# FPGA_Banks_DDR3.net
KiCad netlist of a schematic drawn in Altium Designer
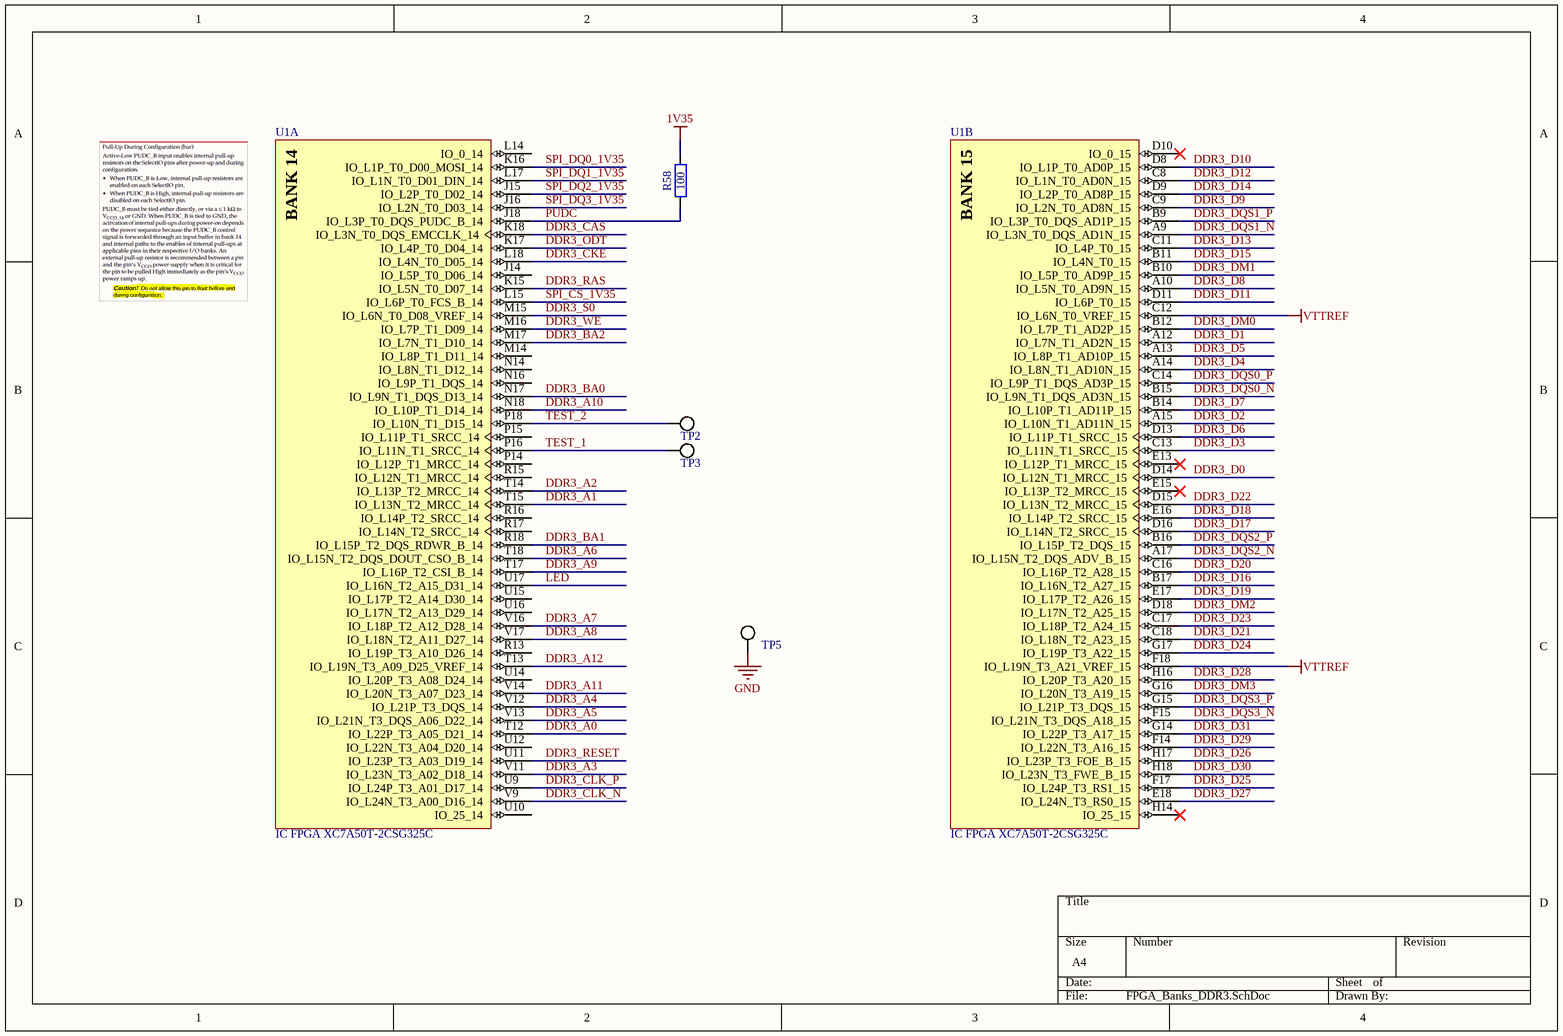
[diagram p0: FPGA_Banks_DDR3.SchDoc]

(export (version "E")
  (design (tool "Eeschema 10.0.6"))
  (components
    (comp (ref "R58")
      (value "100")
      (footprint "GEN_R_0201")
      (fields
        (field (name "TOLERANCE") "1%")
        (field (name "HOUSE PART NUMBER") "R-100-0201-1%-001")
        (field (name "MANUFACTURER") "Yageo")
      )
      (libsource (lib "DSO") (part "RES 100 OHM 1% 1/20W 0201"))
    )
    (comp (ref "TP2") (value "PCB") (footprint "GEN_TP_PCB") (libsource (lib "DSO") (part "TP PCB 1mm")))
    (comp (ref "TP3") (value "PCB") (footprint "GEN_TP_PCB") (libsource (lib "DSO") (part "TP PCB 1mm")))
    (comp (ref "TP5") (value "PCB") (footprint "GEN_TP_PCB") (libsource (lib "DSO") (part "TP PCB 1mm")))
    (comp (ref "U1")
      (value "IC FPGA XC7A50T-2CSG325C")
      (footprint "XILINX_XC7A50T-2CSG325C")
      (description "Artix-7 FPGA, 150 User I/Os, 4 GTP, 324-Ball BGA, Speed Grade 2, Commercial Grade, Pb-Free")
      (fields (field (name "MANUFACTURER") "Xilinx") (field (name "HOUSE PART NUMBER") "XC7A50T-2CSG325C"))
      (libsource (lib "DSO") (part "IC FPGA XC7A50T-2CSG325C"))
    )
  )
  (nets
    (net (code "1") (name "/DDR3_A0") (class "Default")
      (node (ref "U1") (pin "T12") (pinfunction "IO_L22P_T3_A05_D21_14_T12") (pintype "bidirectional"))
    )
    (net (code "2") (name "/DDR3_A1") (class "Default")
      (node (ref "U1") (pin "T15") (pinfunction "IO_L13N_T2_MRCC_14_T15") (pintype "bidirectional"))
    )
    (net (code "3") (name "/DDR3_A2") (class "Default")
      (node (ref "U1") (pin "T14") (pinfunction "IO_L13P_T2_MRCC_14_T14") (pintype "bidirectional"))
    )
    (net (code "4") (name "/DDR3_A3") (class "Default")
      (node (ref "U1") (pin "V11") (pinfunction "IO_L23N_T3_A02_D18_14_V11") (pintype "bidirectional"))
    )
    (net (code "5") (name "/DDR3_A4") (class "Default")
      (node (ref "U1") (pin "V12") (pinfunction "IO_L21P_T3_DQS_14_V12") (pintype "bidirectional"))
    )
    (net (code "6") (name "/DDR3_A5") (class "Default")
      (node (ref "U1") (pin "V13") (pinfunction "IO_L21N_T3_DQS_A06_D22_14_V13") (pintype "bidirectional"))
    )
    (net (code "7") (name "/DDR3_A6") (class "Default")
      (node (ref "U1") (pin "T18") (pinfunction "IO_L15N_T2_DQS_DOUT_CSO_B_14_T18") (pintype "bidirectional"))
    )
    (net (code "8") (name "/DDR3_A7") (class "Default")
      (node (ref "U1") (pin "V16") (pinfunction "IO_L18P_T2_A12_D28_14_V16") (pintype "bidirectional"))
    )
    (net (code "9") (name "/DDR3_A8") (class "Default")
      (node (ref "U1") (pin "V17") (pinfunction "IO_L18N_T2_A11_D27_14_V17") (pintype "bidirectional"))
    )
    (net (code "10") (name "/DDR3_A9") (class "Default")
      (node (ref "U1") (pin "T17") (pinfunction "IO_L16P_T2_CSI_B_14_T17") (pintype "bidirectional"))
    )
    (net (code "11") (name "/DDR3_A10") (class "Default")
      (node (ref "U1") (pin "N18") (pinfunction "IO_L10P_T1_D14_14_N18") (pintype "bidirectional"))
    )
    (net (code "12") (name "/DDR3_A11") (class "Default")
      (node (ref "U1") (pin "V14") (pinfunction "IO_L20N_T3_A07_D23_14_V14") (pintype "bidirectional"))
    )
    (net (code "13") (name "/DDR3_A12") (class "Default")
      (node (ref "U1") (pin "T13") (pinfunction "IO_L19N_T3_A09_D25_VREF_14_T13") (pintype "bidirectional"))
    )
    (net (code "14") (name "/DDR3_BA0") (class "Default")
      (node (ref "U1") (pin "N17") (pinfunction "IO_L9N_T1_DQS_D13_14_N17") (pintype "bidirectional"))
    )
    (net (code "15") (name "/DDR3_BA1") (class "Default")
      (node (ref "U1") (pin "R18") (pinfunction "IO_L15P_T2_DQS_RDWR_B_14_R18") (pintype "bidirectional"))
    )
    (net (code "16") (name "/DDR3_BA2") (class "Default")
      (node (ref "U1") (pin "M17") (pinfunction "IO_L7N_T1_D10_14_M17") (pintype "bidirectional"))
    )
    (net (code "17") (name "/DDR3_CAS") (class "Default")
      (node (ref "U1") (pin "K18") (pinfunction "IO_L3N_T0_DQS_EMCCLK_14_K18") (pintype "bidirectional"))
    )
    (net (code "18") (name "/DDR3_CKE") (class "Default")
      (node (ref "U1") (pin "L18") (pinfunction "IO_L4N_T0_D05_14_L18") (pintype "bidirectional"))
    )
    (net (code "19") (name "/DDR3_CLK_N") (class "Default")
      (node (ref "U1") (pin "V9") (pinfunction "IO_L24N_T3_A00_D16_14_V9") (pintype "bidirectional"))
    )
    (net (code "20") (name "/DDR3_CLK_P") (class "Default")
      (node (ref "U1") (pin "U9") (pinfunction "IO_L24P_T3_A01_D17_14_U9") (pintype "bidirectional"))
    )
    (net (code "21") (name "/DDR3_D0") (class "Default")
      (node (ref "U1") (pin "D14") (pinfunction "IO_L12N_T1_MRCC_15_D14") (pintype "bidirectional"))
    )
    (net (code "22") (name "/DDR3_D1") (class "Default")
      (node (ref "U1") (pin "A12") (pinfunction "IO_L7N_T1_AD2N_15_A12") (pintype "bidirectional"))
    )
    (net (code "23") (name "/DDR3_D2") (class "Default")
      (node (ref "U1") (pin "A15") (pinfunction "IO_L10N_T1_AD11N_15_A15") (pintype "bidirectional"))
    )
    (net (code "24") (name "/DDR3_D3") (class "Default")
      (node (ref "U1") (pin "C13") (pinfunction "IO_L11N_T1_SRCC_15_C13") (pintype "bidirectional"))
    )
    (net (code "25") (name "/DDR3_D4") (class "Default")
      (node (ref "U1") (pin "A14") (pinfunction "IO_L8N_T1_AD10N_15_A14") (pintype "bidirectional"))
    )
    (net (code "26") (name "/DDR3_D5") (class "Default")
      (node (ref "U1") (pin "A13") (pinfunction "IO_L8P_T1_AD10P_15_A13") (pintype "bidirectional"))
    )
    (net (code "27") (name "/DDR3_D6") (class "Default")
      (node (ref "U1") (pin "D13") (pinfunction "IO_L11P_T1_SRCC_15_D13") (pintype "bidirectional"))
    )
    (net (code "28") (name "/DDR3_D7") (class "Default")
      (node (ref "U1") (pin "B14") (pinfunction "IO_L10P_T1_AD11P_15_B14") (pintype "bidirectional"))
    )
    (net (code "29") (name "/DDR3_D8") (class "Default")
      (node (ref "U1") (pin "A10") (pinfunction "IO_L5N_T0_AD9N_15_A10") (pintype "bidirectional"))
    )
    (net (code "30") (name "/DDR3_D9") (class "Default")
      (node (ref "U1") (pin "C9") (pinfunction "IO_L2N_T0_AD8N_15_C9") (pintype "bidirectional"))
    )
    (net (code "31") (name "/DDR3_D10") (class "Default")
      (node (ref "U1") (pin "D8") (pinfunction "IO_L1P_T0_AD0P_15_D8") (pintype "bidirectional"))
    )
    (net (code "32") (name "/DDR3_D11") (class "Default")
      (node (ref "U1") (pin "D11") (pinfunction "IO_L6P_T0_15_D11") (pintype "bidirectional"))
    )
    (net (code "33") (name "/DDR3_D12") (class "Default")
      (node (ref "U1") (pin "C8") (pinfunction "IO_L1N_T0_AD0N_15_C8") (pintype "bidirectional"))
    )
    (net (code "34") (name "/DDR3_D13") (class "Default")
      (node (ref "U1") (pin "C11") (pinfunction "IO_L4P_T0_15_C11") (pintype "bidirectional"))
    )
    (net (code "35") (name "/DDR3_D14") (class "Default")
      (node (ref "U1") (pin "D9") (pinfunction "IO_L2P_T0_AD8P_15_D9") (pintype "bidirectional"))
    )
    (net (code "36") (name "/DDR3_D15") (class "Default")
      (node (ref "U1") (pin "B11") (pinfunction "IO_L4N_T0_15_B11") (pintype "bidirectional"))
    )
    (net (code "37") (name "/DDR3_D16") (class "Default")
      (node (ref "U1") (pin "B17") (pinfunction "IO_L16N_T2_A27_15_B17") (pintype "bidirectional"))
    )
    (net (code "38") (name "/DDR3_D17") (class "Default")
      (node (ref "U1") (pin "D16") (pinfunction "IO_L14N_T2_SRCC_15_D16") (pintype "bidirectional"))
    )
    (net (code "39") (name "/DDR3_D18") (class "Default")
      (node (ref "U1") (pin "E16") (pinfunction "IO_L14P_T2_SRCC_15_E16") (pintype "bidirectional"))
    )
    (net (code "40") (name "/DDR3_D19") (class "Default")
      (node (ref "U1") (pin "E17") (pinfunction "IO_L17P_T2_A26_15_E17") (pintype "bidirectional"))
    )
    (net (code "41") (name "/DDR3_D20") (class "Default")
      (node (ref "U1") (pin "C16") (pinfunction "IO_L16P_T2_A28_15_C16") (pintype "bidirectional"))
    )
    (net (code "42") (name "/DDR3_D21") (class "Default")
      (node (ref "U1") (pin "C18") (pinfunction "IO_L18N_T2_A23_15_C18") (pintype "bidirectional"))
    )
    (net (code "43") (name "/DDR3_D22") (class "Default")
      (node (ref "U1") (pin "D15") (pinfunction "IO_L13N_T2_MRCC_15_D15") (pintype "bidirectional"))
    )
    (net (code "44") (name "/DDR3_D23") (class "Default")
      (node (ref "U1") (pin "C17") (pinfunction "IO_L18P_T2_A24_15_C17") (pintype "bidirectional"))
    )
    (net (code "45") (name "/DDR3_D24") (class "Default")
      (node (ref "U1") (pin "G17") (pinfunction "IO_L19P_T3_A22_15_G17") (pintype "bidirectional"))
    )
    (net (code "46") (name "/DDR3_D25") (class "Default")
      (node (ref "U1") (pin "F17") (pinfunction "IO_L24P_T3_RS1_15_F17") (pintype "bidirectional"))
    )
    (net (code "47") (name "/DDR3_D26") (class "Default")
      (node (ref "U1") (pin "H17") (pinfunction "IO_L23P_T3_FOE_B_15_H17") (pintype "bidirectional"))
    )
    (net (code "48") (name "/DDR3_D27") (class "Default")
      (node (ref "U1") (pin "E18") (pinfunction "IO_L24N_T3_RS0_15_E18") (pintype "bidirectional"))
    )
    (net (code "49") (name "/DDR3_D28") (class "Default")
      (node (ref "U1") (pin "H16") (pinfunction "IO_L20P_T3_A20_15_H16") (pintype "bidirectional"))
    )
    (net (code "50") (name "/DDR3_D29") (class "Default")
      (node (ref "U1") (pin "F14") (pinfunction "IO_L22N_T3_A16_15_F14") (pintype "bidirectional"))
    )
    (net (code "51") (name "/DDR3_D30") (class "Default")
      (node (ref "U1") (pin "H18") (pinfunction "IO_L23N_T3_FWE_B_15_H18") (pintype "bidirectional"))
    )
    (net (code "52") (name "/DDR3_D31") (class "Default")
      (node (ref "U1") (pin "G14") (pinfunction "IO_L22P_T3_A17_15_G14") (pintype "bidirectional"))
    )
    (net (code "53") (name "/DDR3_DM0") (class "Default")
      (node (ref "U1") (pin "B12") (pinfunction "IO_L7P_T1_AD2P_15_B12") (pintype "bidirectional"))
    )
    (net (code "54") (name "/DDR3_DM1") (class "Default")
      (node (ref "U1") (pin "B10") (pinfunction "IO_L5P_T0_AD9P_15_B10") (pintype "bidirectional"))
    )
    (net (code "55") (name "/DDR3_DM2") (class "Default")
      (node (ref "U1") (pin "D18") (pinfunction "IO_L17N_T2_A25_15_D18") (pintype "bidirectional"))
    )
    (net (code "56") (name "/DDR3_DM3") (class "Default")
      (node (ref "U1") (pin "G16") (pinfunction "IO_L20N_T3_A19_15_G16") (pintype "bidirectional"))
    )
    (net (code "57") (name "/DDR3_DQS0_N") (class "Default")
      (node (ref "U1") (pin "B15") (pinfunction "IO_L9N_T1_DQS_AD3N_15_B15") (pintype "bidirectional"))
    )
    (net (code "58") (name "/DDR3_DQS0_P") (class "Default")
      (node (ref "U1") (pin "C14") (pinfunction "IO_L9P_T1_DQS_AD3P_15_C14") (pintype "bidirectional"))
    )
    (net (code "59") (name "/DDR3_DQS1_N") (class "Default")
      (node (ref "U1") (pin "A9") (pinfunction "IO_L3N_T0_DQS_AD1N_15_A9") (pintype "bidirectional"))
    )
    (net (code "60") (name "/DDR3_DQS1_P") (class "Default")
      (node (ref "U1") (pin "B9") (pinfunction "IO_L3P_T0_DQS_AD1P_15_B9") (pintype "bidirectional"))
    )
    (net (code "61") (name "/DDR3_DQS2_N") (class "Default")
      (node (ref "U1") (pin "A17") (pinfunction "IO_L15N_T2_DQS_ADV_B_15_A17") (pintype "bidirectional"))
    )
    (net (code "62") (name "/DDR3_DQS2_P") (class "Default")
      (node (ref "U1") (pin "B16") (pinfunction "IO_L15P_T2_DQS_15_B16") (pintype "bidirectional"))
    )
    (net (code "63") (name "/DDR3_DQS3_N") (class "Default")
      (node (ref "U1") (pin "F15") (pinfunction "IO_L21N_T3_DQS_A18_15_F15") (pintype "bidirectional"))
    )
    (net (code "64") (name "/DDR3_DQS3_P") (class "Default")
      (node (ref "U1") (pin "G15") (pinfunction "IO_L21P_T3_DQS_15_G15") (pintype "bidirectional"))
    )
    (net (code "65") (name "/DDR3_ODT") (class "Default")
      (node (ref "U1") (pin "K17") (pinfunction "IO_L4P_T0_D04_14_K17") (pintype "bidirectional"))
    )
    (net (code "66") (name "/DDR3_RAS") (class "Default")
      (node (ref "U1") (pin "K15") (pinfunction "IO_L5N_T0_D07_14_K15") (pintype "bidirectional"))
    )
    (net (code "67") (name "/DDR3_RESET") (class "Default")
      (node (ref "U1") (pin "U11") (pinfunction "IO_L23P_T3_A03_D19_14_U11") (pintype "bidirectional"))
    )
    (net (code "68") (name "/DDR3_S0") (class "Default")
      (node (ref "U1") (pin "M15") (pinfunction "IO_L6N_T0_D08_VREF_14_M15") (pintype "bidirectional"))
    )
    (net (code "69") (name "/DDR3_WE") (class "Default")
      (node (ref "U1") (pin "M16") (pinfunction "IO_L7P_T1_D09_14_M16") (pintype "bidirectional"))
    )
    (net (code "70") (name "/LED") (class "Default")
      (node (ref "U1") (pin "U17") (pinfunction "IO_L16N_T2_A15_D31_14_U17") (pintype "bidirectional"))
    )
    (net (code "71") (name "/PUDC") (class "Default")
      (node (ref "R58") (pin "1") (pinfunction "1_1") (pintype "passive"))
      (node (ref "U1") (pin "J18") (pinfunction "IO_L3P_T0_DQS_PUDC_B_14_J18") (pintype "bidirectional"))
    )
    (net (code "72") (name "/SPI_CS_1V35") (class "Default")
      (node (ref "U1") (pin "L15") (pinfunction "IO_L6P_T0_FCS_B_14_L15") (pintype "bidirectional"))
    )
    (net (code "73") (name "/SPI_DQ0_1V35") (class "Default")
      (node (ref "U1") (pin "K16") (pinfunction "IO_L1P_T0_D00_MOSI_14_K16") (pintype "bidirectional"))
    )
    (net (code "74") (name "/SPI_DQ1_1V35") (class "Default")
      (node (ref "U1") (pin "L17") (pinfunction "IO_L1N_T0_D01_DIN_14_L17") (pintype "bidirectional"))
    )
    (net (code "75") (name "/SPI_DQ2_1V35") (class "Default")
      (node (ref "U1") (pin "J15") (pinfunction "IO_L2P_T0_D02_14_J15") (pintype "bidirectional"))
    )
    (net (code "76") (name "/SPI_DQ3_1V35") (class "Default")
      (node (ref "U1") (pin "J16") (pinfunction "IO_L2N_T0_D03_14_J16") (pintype "bidirectional"))
    )
    (net (code "77") (name "/TEST_1") (class "Default")
      (node (ref "TP3") (pin "1") (pinfunction "1_1") (pintype "passive"))
      (node (ref "U1") (pin "P16") (pinfunction "IO_L11N_T1_SRCC_14_P16") (pintype "bidirectional"))
    )
    (net (code "78") (name "/TEST_2") (class "Default")
      (node (ref "TP2") (pin "1") (pinfunction "1_1") (pintype "passive"))
      (node (ref "U1") (pin "P18") (pinfunction "IO_L10N_T1_D15_14_P18") (pintype "bidirectional"))
    )
    (net (code "79") (name "1V35") (class "Default")
      (node (ref "R58") (pin "2") (pinfunction "2_2") (pintype "passive"))
    )
    (net (code "80") (name "GND") (class "Default")
      (node (ref "TP5") (pin "1") (pinfunction "1_1") (pintype "passive"))
    )
    (net (code "81") (name "VTTREF") (class "Default")
      (node (ref "U1") (pin "C12") (pinfunction "IO_L6N_T0_VREF_15_C12") (pintype "bidirectional"))
      (node (ref "U1") (pin "F18") (pinfunction "IO_L19N_T3_A21_VREF_15_F18") (pintype "bidirectional"))
    )
    (net (code "82") (name "unconnected-(U1A-IO_0_14-PadL14)") (class "Default")
      (node (ref "U1") (pin "L14") (pinfunction "IO_0_14_L14") (pintype "bidirectional"))
    )
    (net (code "83") (name "unconnected-(U1A-IO_25_14-PadU10)") (class "Default")
      (node (ref "U1") (pin "U10") (pinfunction "IO_25_14_U10") (pintype "bidirectional"))
    )
    (net (code "84") (name "unconnected-(U1A-IO_L5P_T0_D06_14-PadJ14)") (class "Default")
      (node (ref "U1") (pin "J14") (pinfunction "IO_L5P_T0_D06_14_J14") (pintype "bidirectional"))
    )
    (net (code "85") (name "unconnected-(U1A-IO_L8N_T1_D12_14-PadN14)") (class "Default")
      (node (ref "U1") (pin "N14") (pinfunction "IO_L8N_T1_D12_14_N14") (pintype "bidirectional"))
    )
    (net (code "86") (name "unconnected-(U1A-IO_L8P_T1_D11_14-PadM14)") (class "Default")
      (node (ref "U1") (pin "M14") (pinfunction "IO_L8P_T1_D11_14_M14") (pintype "bidirectional"))
    )
    (net (code "87") (name "unconnected-(U1A-IO_L9P_T1_DQS_14-PadN16)") (class "Default")
      (node (ref "U1") (pin "N16") (pinfunction "IO_L9P_T1_DQS_14_N16") (pintype "bidirectional"))
    )
    (net (code "88") (name "unconnected-(U1A-IO_L11P_T1_SRCC_14-PadP15)") (class "Default")
      (node (ref "U1") (pin "P15") (pinfunction "IO_L11P_T1_SRCC_14_P15") (pintype "bidirectional"))
    )
    (net (code "89") (name "unconnected-(U1A-IO_L12N_T1_MRCC_14-PadR15)") (class "Default")
      (node (ref "U1") (pin "R15") (pinfunction "IO_L12N_T1_MRCC_14_R15") (pintype "bidirectional"))
    )
    (net (code "90") (name "unconnected-(U1A-IO_L12P_T1_MRCC_14-PadP14)") (class "Default")
      (node (ref "U1") (pin "P14") (pinfunction "IO_L12P_T1_MRCC_14_P14") (pintype "bidirectional"))
    )
    (net (code "91") (name "unconnected-(U1A-IO_L14N_T2_SRCC_14-PadR17)") (class "Default")
      (node (ref "U1") (pin "R17") (pinfunction "IO_L14N_T2_SRCC_14_R17") (pintype "bidirectional"))
    )
    (net (code "92") (name "unconnected-(U1A-IO_L14P_T2_SRCC_14-PadR16)") (class "Default")
      (node (ref "U1") (pin "R16") (pinfunction "IO_L14P_T2_SRCC_14_R16") (pintype "bidirectional"))
    )
    (net (code "93") (name "unconnected-(U1A-IO_L17N_T2_A13_D29_14-PadU16)") (class "Default")
      (node (ref "U1") (pin "U16") (pinfunction "IO_L17N_T2_A13_D29_14_U16") (pintype "bidirectional"))
    )
    (net (code "94") (name "unconnected-(U1A-IO_L17P_T2_A14_D30_14-PadU15)") (class "Default")
      (node (ref "U1") (pin "U15") (pinfunction "IO_L17P_T2_A14_D30_14_U15") (pintype "bidirectional"))
    )
    (net (code "95") (name "unconnected-(U1A-IO_L19P_T3_A10_D26_14-PadR13)") (class "Default")
      (node (ref "U1") (pin "R13") (pinfunction "IO_L19P_T3_A10_D26_14_R13") (pintype "bidirectional"))
    )
    (net (code "96") (name "unconnected-(U1A-IO_L20P_T3_A08_D24_14-PadU14)") (class "Default")
      (node (ref "U1") (pin "U14") (pinfunction "IO_L20P_T3_A08_D24_14_U14") (pintype "bidirectional"))
    )
    (net (code "97") (name "unconnected-(U1A-IO_L22N_T3_A04_D20_14-PadU12)") (class "Default")
      (node (ref "U1") (pin "U12") (pinfunction "IO_L22N_T3_A04_D20_14_U12") (pintype "bidirectional"))
    )
    (net (code "98") (name "unconnected-(U1B-IO_0_15-PadD10)") (class "Default")
      (node (ref "U1") (pin "D10") (pinfunction "IO_0_15_D10") (pintype "bidirectional+no_connect"))
    )
    (net (code "99") (name "unconnected-(U1B-IO_25_15-PadH14)") (class "Default")
      (node (ref "U1") (pin "H14") (pinfunction "IO_25_15_H14") (pintype "bidirectional+no_connect"))
    )
    (net (code "100") (name "unconnected-(U1B-IO_L12P_T1_MRCC_15-PadE13)") (class "Default")
      (node (ref "U1") (pin "E13") (pinfunction "IO_L12P_T1_MRCC_15_E13") (pintype "bidirectional+no_connect"))
    )
    (net (code "101") (name "unconnected-(U1B-IO_L13P_T2_MRCC_15-PadE15)") (class "Default")
      (node (ref "U1") (pin "E15") (pinfunction "IO_L13P_T2_MRCC_15_E15") (pintype "bidirectional+no_connect"))
    )
  )
)
